# SYSTEM.net
KiCad netlist of a schematic drawn in Altium Designer
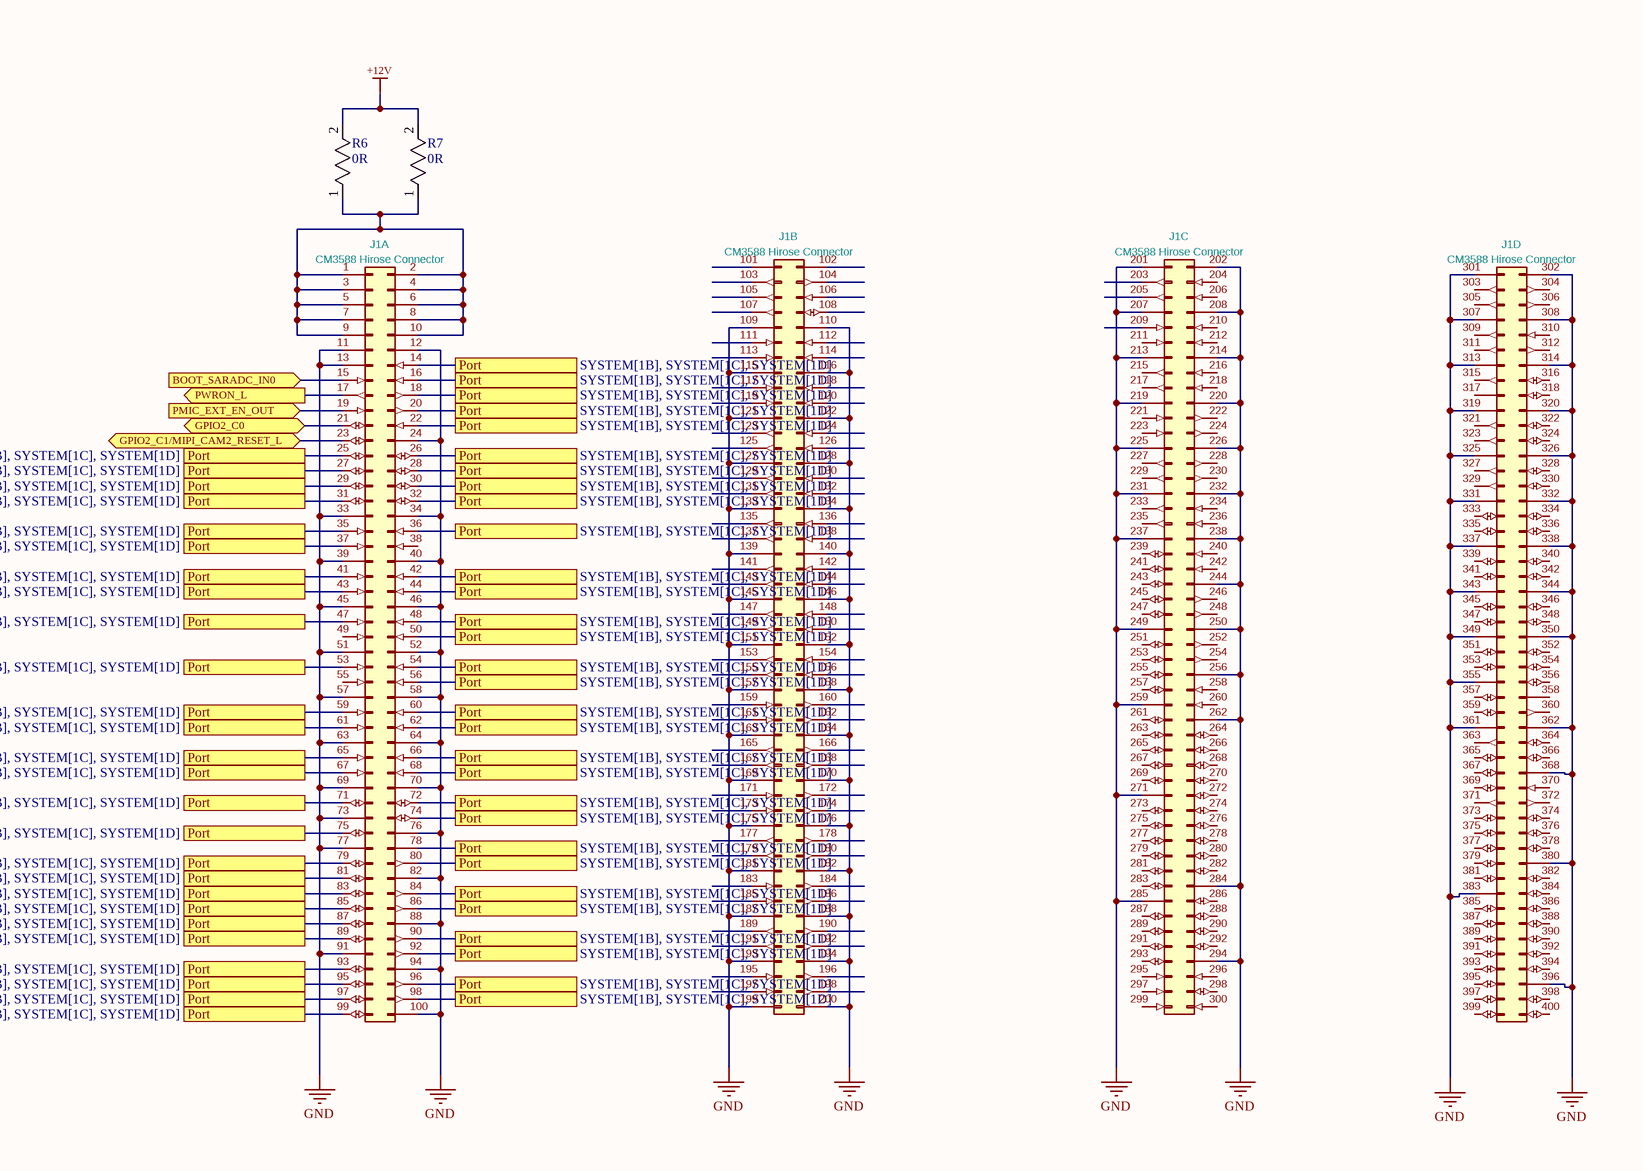
[diagram p0: SYSTEM.SchDoc, right]

(export (version "E")
  (design (tool "Eeschema 10.0.6"))
  (components
    (comp (ref "J1")
      (value "CM3588 Hirose Connector")
      (footprint "CM3588")
      (libsource (lib "cm3588") (part "CM3588"))
    )
    (comp (ref "R6")
      (value "0R")
      (footprint "RES_0816_SUS")
      (description "Zero Ohm Resistor, Jumper, 0603 [1608 Metric], Thick Film, 100 mW, 1 A, Surface Mount")
      (fields
        (field (name "MANUFACTURER") "NIC Components")
        (field (name "MANUFACTURER PART NUMBER") "NRC06ZOTRF")
      )
      (libsource (lib "RES_SMD_0603") (part "RG1608P-104-B-T5"))
    )
    (comp (ref "R7")
      (value "0R")
      (footprint "RES_0816_SUS")
      (description "Zero Ohm Resistor, Jumper, 0603 [1608 Metric], Thick Film, 100 mW, 1 A, Surface Mount")
      (fields
        (field (name "MANUFACTURER") "NIC Components")
        (field (name "MANUFACTURER PART NUMBER") "NRC06ZOTRF")
      )
      (libsource (lib "RES_SMD_0603") (part "RG1608P-104-B-T5"))
    )
  )
  (nets
    (net (code "1") (name "+12V") (class "Default")
      (node (ref "R6") (pin "2") (pinfunction "2_2") (pintype "passive"))
      (node (ref "R7") (pin "2") (pinfunction "2_2") (pintype "passive"))
    )
    (net (code "2") (name "/BOOT_SARADC_IN0") (class "Default")
      (node (ref "J1") (pin "15") (pinfunction "BOOT_SARADC_IN0_15") (pintype "input"))
    )
    (net (code "3") (name "/GPIO2_C0") (class "Default")
      (node (ref "J1") (pin "21") (pinfunction "GPIO2_C0_21") (pintype "bidirectional"))
    )
    (net (code "4") (name "/GPIO2_C1{slash}MIPI_CAM2_RESET_L") (class "Default")
      (node (ref "J1") (pin "23") (pinfunction "GPIO2_C1/MIPI_CAM2_RESET_L_23") (pintype "bidirectional"))
    )
    (net (code "5") (name "/PMIC_EXT_EN_OUT") (class "Default")
      (node (ref "J1") (pin "19") (pinfunction "PMIC_EXT_EN_OUT_19") (pintype "input"))
    )
    (net (code "6") (name "/PWRON_L") (class "Default")
      (node (ref "J1") (pin "17") (pinfunction "PWRON_L_17") (pintype "output"))
    )
    (net (code "7") (name "/Port") (class "Default")
      (node (ref "J1") (pin "14") (pinfunction "SARADC_VIN6_HW_ID2_14") (pintype "input"))
      (node (ref "J1") (pin "16") (pinfunction "RESET_L_16") (pintype "input"))
      (node (ref "J1") (pin "18") (pinfunction "VDC_MODE_18") (pintype "output"))
      (node (ref "J1") (pin "20") (pinfunction "UART2_TX_M0_DEBUG_20") (pintype "output"))
      (node (ref "J1") (pin "22") (pinfunction "UART2_RX_M0_DEBUG_22") (pintype "input"))
      (node (ref "J1") (pin "25") (pinfunction "GPIO2_C2/MIPI_CAM2_PDN_L_25") (pintype "bidirectional"))
      (node (ref "J1") (pin "26") (pinfunction "GPIO4_C2_26") (pintype "bidirectional"))
      (node (ref "J1") (pin "27") (pinfunction "GPIO2_C3_27") (pintype "bidirectional"))
      (node (ref "J1") (pin "28") (pinfunction "GPIO4_C3_28") (pintype "bidirectional"))
      (node (ref "J1") (pin "29") (pinfunction "GPIO2_C4_29") (pintype "bidirectional"))
      (node (ref "J1") (pin "30") (pinfunction "GPIO4_C4_30") (pintype "bidirectional"))
      (node (ref "J1") (pin "31") (pinfunction "GPIO4_C6_31") (pintype "bidirectional"))
      (node (ref "J1") (pin "32") (pinfunction "GPIO4_C5_32") (pintype "bidirectional"))
      (node (ref "J1") (pin "35") (pinfunction "MIPI_CSI1_RX_CLK1P_35") (pintype "input"))
      (node (ref "J1") (pin "36") (pinfunction "MIPI_CSI0_RX_CLK1P_36") (pintype "input"))
      (node (ref "J1") (pin "37") (pinfunction "MIPI_CSI1_RX_CLK1N_37") (pintype "input"))
      (node (ref "J1") (pin "41") (pinfunction "MIPI_CSI1_RX_D3P_41") (pintype "input"))
      (node (ref "J1") (pin "42") (pinfunction "MIPI_CSI0_RX_D3P_42") (pintype "input"))
      (node (ref "J1") (pin "43") (pinfunction "MIPI_CSI1_RX_D3N_43") (pintype "input"))
      (node (ref "J1") (pin "44") (pinfunction "MIPI_CSI0_RX_D3N_44") (pintype "input"))
      (node (ref "J1") (pin "47") (pinfunction "MIPI_CSI1_RX_D2P_47") (pintype "input"))
      (node (ref "J1") (pin "48") (pinfunction "MIPI_CSI0_RX_D2P_48") (pintype "input"))
      (node (ref "J1") (pin "50") (pinfunction "MIPI_CSI0_RX_D2N_50") (pintype "input"))
      (node (ref "J1") (pin "53") (pinfunction "MIPI_CSI1_RX_CLK0P_53") (pintype "input"))
      (node (ref "J1") (pin "54") (pinfunction "MIPI_CSI0_RX_CLK0P_54") (pintype "input"))
      (node (ref "J1") (pin "56") (pinfunction "MIPI_CSI0_RX_CLK0N_56") (pintype "input"))
      (node (ref "J1") (pin "59") (pinfunction "MIPI_CSI1_RX_D1P_59") (pintype "input"))
      (node (ref "J1") (pin "60") (pinfunction "MIPI_CSI0_RX_D1P_60") (pintype "input"))
      (node (ref "J1") (pin "61") (pinfunction "MIPI_CSI1_RX_D1N_61") (pintype "input"))
      (node (ref "J1") (pin "62") (pinfunction "MIPI_CSI0_RX_D1N_62") (pintype "input"))
      (node (ref "J1") (pin "65") (pinfunction "MIPI_CSI1_RX_D0P_65") (pintype "input"))
      (node (ref "J1") (pin "66") (pinfunction "MIPI_CSI0_RX_D0P_66") (pintype "input"))
      (node (ref "J1") (pin "67") (pinfunction "MIPI_CSI1_RX_D0N_67") (pintype "input"))
      (node (ref "J1") (pin "68") (pinfunction "MIPI_CSI0_RX_D0N_68") (pintype "input"))
      (node (ref "J1") (pin "71") (pinfunction "GPIO1_B6_71") (pintype "bidirectional"))
      (node (ref "J1") (pin "72") (pinfunction "LED3_25GLAN_25GLED_72") (pintype "bidirectional"))
      (node (ref "J1") (pin "74") (pinfunction "LED2_25GLAN_1GLED_74") (pintype "bidirectional"))
      (node (ref "J1") (pin "75") (pinfunction "GPIO1_B7_75") (pintype "bidirectional"))
      (node (ref "J1") (pin "78") (pinfunction "P25G_MDIP0_78") (pintype "passive"))
      (node (ref "J1") (pin "79") (pinfunction "GPIO2_A6_79") (pintype "bidirectional"))
      (node (ref "J1") (pin "80") (pinfunction "P25G_MDIN0_80") (pintype "output"))
      (node (ref "J1") (pin "81") (pinfunction "GPIO2_A7_81") (pintype "bidirectional"))
      (node (ref "J1") (pin "83") (pinfunction "GPIO2_B0_83") (pintype "bidirectional"))
      (node (ref "J1") (pin "84") (pinfunction "P25G_MDIP1_84") (pintype "output"))
      (node (ref "J1") (pin "85") (pinfunction "GPIO2_B1_GPIO,_85") (pintype "bidirectional"))
      (node (ref "J1") (pin "86") (pinfunction "P25G_MDIN1_86") (pintype "output"))
      (node (ref "J1") (pin "87") (pinfunction "GPIO2_B2_87") (pintype "bidirectional"))
      (node (ref "J1") (pin "89") (pinfunction "GPIO2_B3_89") (pintype "bidirectional"))
      (node (ref "J1") (pin "90") (pinfunction "P25G_MDIP2_90") (pintype "output"))
      (node (ref "J1") (pin "92") (pinfunction "P25G_MDIN2_92") (pintype "output"))
      (node (ref "J1") (pin "93") (pinfunction "GPIO2_B4_93") (pintype "bidirectional"))
      (node (ref "J1") (pin "95") (pinfunction "GPIO2_B5_95") (pintype "bidirectional"))
      (node (ref "J1") (pin "96") (pinfunction "P25G_MDIP3_96") (pintype "output"))
      (node (ref "J1") (pin "97") (pinfunction "GPIO2_B6_97") (pintype "bidirectional"))
      (node (ref "J1") (pin "98") (pinfunction "P25G_MDIN3_98") (pintype "output"))
      (node (ref "J1") (pin "99") (pinfunction "GPIO2_B7_99") (pintype "bidirectional"))
    )
    (net (code "8") (name "GND") (class "Default")
      (node (ref "J1") (pin "100") (pinfunction "GND_100") (pintype "passive"))
      (node (ref "J1") (pin "109") (pinfunction "GND_109") (pintype "passive"))
      (node (ref "J1") (pin "11") (pinfunction "GND_11") (pintype "passive"))
      (node (ref "J1") (pin "110") (pinfunction "GND_110") (pintype "passive"))
      (node (ref "J1") (pin "115") (pinfunction "GND_115") (pintype "passive"))
      (node (ref "J1") (pin "116") (pinfunction "GND_116") (pintype "passive"))
      (node (ref "J1") (pin "12") (pinfunction "GND_12") (pintype "passive"))
      (node (ref "J1") (pin "121") (pinfunction "GND_121") (pintype "passive"))
      (node (ref "J1") (pin "122") (pinfunction "GND_122") (pintype "passive"))
      (node (ref "J1") (pin "127") (pinfunction "GND_127") (pintype "passive"))
      (node (ref "J1") (pin "128") (pinfunction "GND_128") (pintype "passive"))
      (node (ref "J1") (pin "13") (pinfunction "GND_13") (pintype "passive"))
      (node (ref "J1") (pin "133") (pinfunction "GND_133") (pintype "passive"))
      (node (ref "J1") (pin "134") (pinfunction "GND_134") (pintype "passive"))
      (node (ref "J1") (pin "139") (pinfunction "GND_139") (pintype "passive"))
      (node (ref "J1") (pin "140") (pinfunction "GND_140") (pintype "passive"))
      (node (ref "J1") (pin "145") (pinfunction "GND_145") (pintype "passive"))
      (node (ref "J1") (pin "146") (pinfunction "GND_146") (pintype "passive"))
      (node (ref "J1") (pin "151") (pinfunction "GND_151") (pintype "passive"))
      (node (ref "J1") (pin "152") (pinfunction "GND_152") (pintype "passive"))
      (node (ref "J1") (pin "157") (pinfunction "GND_157") (pintype "passive"))
      (node (ref "J1") (pin "158") (pinfunction "GND_158") (pintype "passive"))
      (node (ref "J1") (pin "163") (pinfunction "GND_163") (pintype "passive"))
      (node (ref "J1") (pin "164") (pinfunction "GND_164") (pintype "passive"))
      (node (ref "J1") (pin "169") (pinfunction "GND_169") (pintype "passive"))
      (node (ref "J1") (pin "170") (pinfunction "GND_170") (pintype "passive"))
      (node (ref "J1") (pin "175") (pinfunction "GND_175") (pintype "passive"))
      (node (ref "J1") (pin "176") (pinfunction "GND_176") (pintype "passive"))
      (node (ref "J1") (pin "181") (pinfunction "GND_181") (pintype "passive"))
      (node (ref "J1") (pin "182") (pinfunction "GND_182") (pintype "passive"))
      (node (ref "J1") (pin "187") (pinfunction "GND_187") (pintype "passive"))
      (node (ref "J1") (pin "188") (pinfunction "GND_188") (pintype "passive"))
      (node (ref "J1") (pin "193") (pinfunction "GND_193") (pintype "passive"))
      (node (ref "J1") (pin "194") (pinfunction "GND_194") (pintype "passive"))
      (node (ref "J1") (pin "199") (pinfunction "GND_199") (pintype "passive"))
      (node (ref "J1") (pin "200") (pinfunction "GND_200") (pintype "passive"))
      (node (ref "J1") (pin "201") (pinfunction "GND_201") (pintype "passive"))
      (node (ref "J1") (pin "202") (pinfunction "GND_202") (pintype "passive"))
      (node (ref "J1") (pin "207") (pinfunction "GND_207") (pintype "passive"))
      (node (ref "J1") (pin "208") (pinfunction "GND_208") (pintype "passive"))
      (node (ref "J1") (pin "213") (pinfunction "GND_213") (pintype "passive"))
      (node (ref "J1") (pin "214") (pinfunction "GND_214") (pintype "passive"))
      (node (ref "J1") (pin "219") (pinfunction "GND_219") (pintype "passive"))
      (node (ref "J1") (pin "220") (pinfunction "GND_220") (pintype "passive"))
      (node (ref "J1") (pin "225") (pinfunction "GND_225") (pintype "passive"))
      (node (ref "J1") (pin "226") (pinfunction "GND_226") (pintype "passive"))
      (node (ref "J1") (pin "231") (pinfunction "GND_231") (pintype "passive"))
      (node (ref "J1") (pin "232") (pinfunction "GND_232") (pintype "passive"))
      (node (ref "J1") (pin "237") (pinfunction "GND_237") (pintype "passive"))
      (node (ref "J1") (pin "238") (pinfunction "GND_238") (pintype "passive"))
      (node (ref "J1") (pin "24") (pinfunction "GND_24") (pintype "passive"))
      (node (ref "J1") (pin "244") (pinfunction "GND_244") (pintype "passive"))
      (node (ref "J1") (pin "249") (pinfunction "GND_249") (pintype "passive"))
      (node (ref "J1") (pin "250") (pinfunction "GND_250") (pintype "passive"))
      (node (ref "J1") (pin "256") (pinfunction "GND_256") (pintype "passive"))
      (node (ref "J1") (pin "259") (pinfunction "GND_259") (pintype "passive"))
      (node (ref "J1") (pin "262") (pinfunction "GND_262") (pintype "passive"))
      (node (ref "J1") (pin "271") (pinfunction "GND_271") (pintype "passive"))
      (node (ref "J1") (pin "284") (pinfunction "GND_284") (pintype "passive"))
      (node (ref "J1") (pin "285") (pinfunction "GND_285") (pintype "passive"))
      (node (ref "J1") (pin "294") (pinfunction "GND_294") (pintype "passive"))
      (node (ref "J1") (pin "301") (pinfunction "GND_301") (pintype "passive"))
      (node (ref "J1") (pin "302") (pinfunction "GND_302") (pintype "passive"))
      (node (ref "J1") (pin "307") (pinfunction "GND_307") (pintype "passive"))
      (node (ref "J1") (pin "308") (pinfunction "GND_308") (pintype "passive"))
      (node (ref "J1") (pin "313") (pinfunction "GND_313") (pintype "passive"))
      (node (ref "J1") (pin "314") (pinfunction "GND_314") (pintype "passive"))
      (node (ref "J1") (pin "319") (pinfunction "GND_319") (pintype "passive"))
      (node (ref "J1") (pin "320") (pinfunction "GND_320") (pintype "passive"))
      (node (ref "J1") (pin "325") (pinfunction "GND_325") (pintype "passive"))
      (node (ref "J1") (pin "326") (pinfunction "GND_326") (pintype "passive"))
      (node (ref "J1") (pin "33") (pinfunction "GND_33") (pintype "power_in"))
      (node (ref "J1") (pin "331") (pinfunction "GND_331") (pintype "passive"))
      (node (ref "J1") (pin "332") (pinfunction "GND_332") (pintype "passive"))
      (node (ref "J1") (pin "337") (pinfunction "GND_337") (pintype "passive"))
      (node (ref "J1") (pin "338") (pinfunction "GND_338") (pintype "passive"))
      (node (ref "J1") (pin "34") (pinfunction "GND_34") (pintype "power_in"))
      (node (ref "J1") (pin "343") (pinfunction "GND_343") (pintype "passive"))
      (node (ref "J1") (pin "344") (pinfunction "GND_344") (pintype "passive"))
      (node (ref "J1") (pin "349") (pinfunction "GND_349") (pintype "passive"))
      (node (ref "J1") (pin "350") (pinfunction "GND_350") (pintype "passive"))
      (node (ref "J1") (pin "355") (pinfunction "GND_355") (pintype "passive"))
      (node (ref "J1") (pin "361") (pinfunction "GND_361") (pintype "passive"))
      (node (ref "J1") (pin "362") (pinfunction "GND_362") (pintype "passive"))
      (node (ref "J1") (pin "368") (pinfunction "GND_368") (pintype "passive"))
      (node (ref "J1") (pin "380") (pinfunction "GND_380") (pintype "passive"))
      (node (ref "J1") (pin "383") (pinfunction "GND_383") (pintype "passive"))
      (node (ref "J1") (pin "39") (pinfunction "GND_39") (pintype "passive"))
      (node (ref "J1") (pin "396") (pinfunction "GND_396") (pintype "passive"))
      (node (ref "J1") (pin "40") (pinfunction "GND_40") (pintype "passive"))
      (node (ref "J1") (pin "45") (pinfunction "GND_45") (pintype "passive"))
      (node (ref "J1") (pin "46") (pinfunction "GND_46") (pintype "passive"))
      (node (ref "J1") (pin "51") (pinfunction "GND_51") (pintype "passive"))
      (node (ref "J1") (pin "52") (pinfunction "GND_52") (pintype "passive"))
      (node (ref "J1") (pin "57") (pinfunction "GND_57") (pintype "passive"))
      (node (ref "J1") (pin "58") (pinfunction "GND_58") (pintype "passive"))
      (node (ref "J1") (pin "63") (pinfunction "GND_63") (pintype "passive"))
      (node (ref "J1") (pin "64") (pinfunction "GND_64") (pintype "passive"))
      (node (ref "J1") (pin "69") (pinfunction "GND_69") (pintype "passive"))
      (node (ref "J1") (pin "70") (pinfunction "GND_70") (pintype "passive"))
      (node (ref "J1") (pin "73") (pinfunction "GND_73") (pintype "passive"))
      (node (ref "J1") (pin "76") (pinfunction "GND_76") (pintype "passive"))
      (node (ref "J1") (pin "77") (pinfunction "GND_77") (pintype "passive"))
      (node (ref "J1") (pin "82") (pinfunction "GND_82") (pintype "passive"))
      (node (ref "J1") (pin "88") (pinfunction "GND_88") (pintype "passive"))
      (node (ref "J1") (pin "91") (pinfunction "GND_91") (pintype "passive"))
      (node (ref "J1") (pin "94") (pinfunction "GND_94") (pintype "passive"))
    )
    (net (code "9") (name "Net-(J1A-VDD_DCIN-Pad1)") (class "Default")
      (node (ref "J1") (pin "1") (pinfunction "VDD_DCIN_1") (pintype "power_in"))
      (node (ref "J1") (pin "10") (pinfunction "VDD_DCIN_10") (pintype "power_in"))
      (node (ref "J1") (pin "2") (pinfunction "VDD_DCIN_2") (pintype "power_in"))
      (node (ref "J1") (pin "3") (pinfunction "VDD_DCIN_3") (pintype "power_in"))
      (node (ref "J1") (pin "4") (pinfunction "VDD_DCIN_4") (pintype "power_in"))
      (node (ref "J1") (pin "5") (pinfunction "VDD_DCIN_5") (pintype "power_in"))
      (node (ref "J1") (pin "6") (pinfunction "VDD_DCIN_6") (pintype "power_in"))
      (node (ref "J1") (pin "7") (pinfunction "VDD_DCIN_7") (pintype "power_in"))
      (node (ref "J1") (pin "8") (pinfunction "VDD_DCIN_8") (pintype "power_in"))
      (node (ref "J1") (pin "9") (pinfunction "VDD_DCIN_9") (pintype "power_in"))
      (node (ref "R6") (pin "1") (pinfunction "1_1") (pintype "passive"))
      (node (ref "R7") (pin "1") (pinfunction "1_1") (pintype "passive"))
    )
    (net (code "10") (name "unconnected-(J1A-MIPI_CSI0_RX_CLK1N-Pad38)") (class "Default")
      (node (ref "J1") (pin "38") (pinfunction "MIPI_CSI0_RX_CLK1N_38") (pintype "input"))
    )
    (net (code "11") (name "unconnected-(J1A-MIPI_CSI1_RX_CLK0N-Pad55)") (class "Default")
      (node (ref "J1") (pin "55") (pinfunction "MIPI_CSI1_RX_CLK0N_55") (pintype "input"))
    )
    (net (code "12") (name "unconnected-(J1A-MIPI_CSI1_RX_D2N-Pad49)") (class "Default")
      (node (ref "J1") (pin "49") (pinfunction "MIPI_CSI1_RX_D2N_49") (pintype "input"))
    )
    (net (code "13") (name "unconnected-(J1B-GND_AUDUO-Pad102)") (class "Default")
      (node (ref "J1") (pin "102") (pinfunction "GND_AUDUO_102") (pintype "passive"))
    )
    (net (code "14") (name "unconnected-(J1B-GPIO1_C4{slash}HP_DET_L-Pad108)") (class "Default")
      (node (ref "J1") (pin "108") (pinfunction "GPIO1_C4/HP_DET_L_108") (pintype "bidirectional"))
    )
    (net (code "15") (name "unconnected-(J1B-HPL-Pad104)") (class "Default")
      (node (ref "J1") (pin "104") (pinfunction "HPL_104") (pintype "output"))
    )
    (net (code "16") (name "unconnected-(J1B-HPR-Pad103)") (class "Default")
      (node (ref "J1") (pin "103") (pinfunction "HPR_103") (pintype "output"))
    )
    (net (code "17") (name "unconnected-(J1B-I2C7_SCL_M0-Pad107)") (class "Default")
      (node (ref "J1") (pin "107") (pinfunction "I2C7_SCL_M0_107") (pintype "output"))
    )
    (net (code "18") (name "unconnected-(J1B-I2C7_SDA_M0-Pad105)") (class "Default")
      (node (ref "J1") (pin "105") (pinfunction "I2C7_SDA_M0_105") (pintype "output"))
    )
    (net (code "19") (name "unconnected-(J1B-MIC_IN-Pad106)") (class "Default")
      (node (ref "J1") (pin "106") (pinfunction "MIC_IN_106") (pintype "input"))
    )
    (net (code "20") (name "unconnected-(J1B-MIPI_DPHY0_RX_CLKN-Pad120)") (class "Default")
      (node (ref "J1") (pin "120") (pinfunction "MIPI_DPHY0_RX_CLKN_120") (pintype "input"))
    )
    (net (code "21") (name "unconnected-(J1B-MIPI_DPHY0_RX_CLKP-Pad118)") (class "Default")
      (node (ref "J1") (pin "118") (pinfunction "MIPI_DPHY0_RX_CLKP_118") (pintype "input"))
    )
    (net (code "22") (name "unconnected-(J1B-MIPI_DPHY0_RX_D0N-Pad126)") (class "Default")
      (node (ref "J1") (pin "126") (pinfunction "MIPI_DPHY0_RX_D0N_126") (pintype "input"))
    )
    (net (code "23") (name "unconnected-(J1B-MIPI_DPHY0_RX_D0P-Pad124)") (class "Default")
      (node (ref "J1") (pin "124") (pinfunction "MIPI_DPHY0_RX_D0P_124") (pintype "input"))
    )
    (net (code "24") (name "unconnected-(J1B-MIPI_DPHY0_RX_D1N-Pad119)") (class "Default")
      (node (ref "J1") (pin "119") (pinfunction "MIPI_DPHY0_RX_D1N_119") (pintype "input"))
    )
    (net (code "25") (name "unconnected-(J1B-MIPI_DPHY0_RX_D1P-Pad117)") (class "Default")
      (node (ref "J1") (pin "117") (pinfunction "MIPI_DPHY0_RX_D1P_117") (pintype "input"))
    )
    (net (code "26") (name "unconnected-(J1B-MIPI_DPHY0_RX_D2N-Pad113)") (class "Default")
      (node (ref "J1") (pin "113") (pinfunction "MIPI_DPHY0_RX_D2N_113") (pintype "input"))
    )
    (net (code "27") (name "unconnected-(J1B-MIPI_DPHY0_RX_D2P-Pad111)") (class "Default")
      (node (ref "J1") (pin "111") (pinfunction "MIPI_DPHY0_RX_D2P_111") (pintype "input"))
    )
    (net (code "28") (name "unconnected-(J1B-MIPI_DPHY0_RX_D3N-Pad114)") (class "Default")
      (node (ref "J1") (pin "114") (pinfunction "MIPI_DPHY0_RX_D3N_114") (pintype "input"))
    )
    (net (code "29") (name "unconnected-(J1B-MIPI_DPHY0_RX_D3P-Pad112)") (class "Default")
      (node (ref "J1") (pin "112") (pinfunction "MIPI_DPHY0_RX_D3P_112") (pintype "input"))
    )
    (net (code "30") (name "unconnected-(J1B-MIPI_DPHY0_TX_CLKN-Pad137)") (class "Default")
      (node (ref "J1") (pin "137") (pinfunction "MIPI_DPHY0_TX_CLKN_137") (pintype "output"))
    )
    (net (code "31") (name "unconnected-(J1B-MIPI_DPHY0_TX_CLKP-Pad135)") (class "Default")
      (node (ref "J1") (pin "135") (pinfunction "MIPI_DPHY0_TX_CLKP_135") (pintype "output"))
    )
    (net (code "32") (name "unconnected-(J1B-MIPI_DPHY0_TX_D0N-Pad149)") (class "Default")
      (node (ref "J1") (pin "149") (pinfunction "MIPI_DPHY0_TX_D0N_149") (pintype "output"))
    )
    (net (code "33") (name "unconnected-(J1B-MIPI_DPHY0_TX_D0P-Pad147)") (class "Default")
      (node (ref "J1") (pin "147") (pinfunction "MIPI_DPHY0_TX_D0P_147") (pintype "output"))
    )
    (net (code "34") (name "unconnected-(J1B-MIPI_DPHY0_TX_D1N-Pad143)") (class "Default")
      (node (ref "J1") (pin "143") (pinfunction "MIPI_DPHY0_TX_D1N_143") (pintype "output"))
    )
    (net (code "35") (name "unconnected-(J1B-MIPI_DPHY0_TX_D1P-Pad141)") (class "Default")
      (node (ref "J1") (pin "141") (pinfunction "MIPI_DPHY0_TX_D1P_141") (pintype "output"))
    )
    (net (code "36") (name "unconnected-(J1B-MIPI_DPHY0_TX_D2N-Pad131)") (class "Default")
      (node (ref "J1") (pin "131") (pinfunction "MIPI_DPHY0_TX_D2N_131") (pintype "output"))
    )
    (net (code "37") (name "unconnected-(J1B-MIPI_DPHY0_TX_D2P-Pad129)") (class "Default")
      (node (ref "J1") (pin "129") (pinfunction "MIPI_DPHY0_TX_D2P_129") (pintype "output"))
    )
    (net (code "38") (name "unconnected-(J1B-MIPI_DPHY0_TX_D3N-Pad125)") (class "Default")
      (node (ref "J1") (pin "125") (pinfunction "MIPI_DPHY0_TX_D3N_125") (pintype "output"))
    )
    (net (code "39") (name "unconnected-(J1B-MIPI_DPHY0_TX_D3P-Pad123)") (class "Default")
      (node (ref "J1") (pin "123") (pinfunction "MIPI_DPHY0_TX_D3P_123") (pintype "output"))
    )
    (net (code "40") (name "unconnected-(J1B-MIPI_DPHY1_RX_CLKN-Pad144)") (class "Default")
      (node (ref "J1") (pin "144") (pinfunction "MIPI_DPHY1_RX_CLKN_144") (pintype "input"))
    )
    (net (code "41") (name "unconnected-(J1B-MIPI_DPHY1_RX_CLKP-Pad142)") (class "Default")
      (node (ref "J1") (pin "142") (pinfunction "MIPI_DPHY1_RX_CLKP_142") (pintype "input"))
    )
    (net (code "42") (name "unconnected-(J1B-MIPI_DPHY1_RX_D0N-Pad156)") (class "Default")
      (node (ref "J1") (pin "156") (pinfunction "MIPI_DPHY1_RX_D0N_156") (pintype "input"))
    )
    (net (code "43") (name "unconnected-(J1B-MIPI_DPHY1_RX_D0P-Pad154)") (class "Default")
      (node (ref "J1") (pin "154") (pinfunction "MIPI_DPHY1_RX_D0P_154") (pintype "input"))
    )
    (net (code "44") (name "unconnected-(J1B-MIPI_DPHY1_RX_D1N-Pad150)") (class "Default")
      (node (ref "J1") (pin "150") (pinfunction "MIPI_DPHY1_RX_D1N_150") (pintype "input"))
    )
    (net (code "45") (name "unconnected-(J1B-MIPI_DPHY1_RX_D1P-Pad148)") (class "Default")
      (node (ref "J1") (pin "148") (pinfunction "MIPI_DPHY1_RX_D1P_148") (pintype "input"))
    )
    (net (code "46") (name "unconnected-(J1B-MIPI_DPHY1_RX_D2N-Pad138)") (class "Default")
      (node (ref "J1") (pin "138") (pinfunction "MIPI_DPHY1_RX_D2N_138") (pintype "input"))
    )
    (net (code "47") (name "unconnected-(J1B-MIPI_DPHY1_RX_D2P-Pad136)") (class "Default")
      (node (ref "J1") (pin "136") (pinfunction "MIPI_DPHY1_RX_D2P_136") (pintype "input"))
    )
    (net (code "48") (name "unconnected-(J1B-MIPI_DPHY1_RX_D3N-Pad132)") (class "Default")
      (node (ref "J1") (pin "132") (pinfunction "MIPI_DPHY1_RX_D3N_132") (pintype "input"))
    )
    (net (code "49") (name "unconnected-(J1B-MIPI_DPHY1_RX_D3P-Pad130)") (class "Default")
      (node (ref "J1") (pin "130") (pinfunction "MIPI_DPHY1_RX_D3P_130") (pintype "input"))
    )
    (net (code "50") (name "unconnected-(J1B-MIPI_DPHY1_TX_CLKN-Pad174)") (class "Default")
      (node (ref "J1") (pin "174") (pinfunction "MIPI_DPHY1_TX_CLKN_174") (pintype "output"))
    )
    (net (code "51") (name "unconnected-(J1B-MIPI_DPHY1_TX_CLKP-Pad172)") (class "Default")
      (node (ref "J1") (pin "172") (pinfunction "MIPI_DPHY1_TX_CLKP_172") (pintype "output"))
    )
    (net (code "52") (name "unconnected-(J1B-MIPI_DPHY1_TX_D0N-Pad186)") (class "Default")
      (node (ref "J1") (pin "186") (pinfunction "MIPI_DPHY1_TX_D0N_186") (pintype "output"))
    )
    (net (code "53") (name "unconnected-(J1B-MIPI_DPHY1_TX_D0P-Pad184)") (class "Default")
      (node (ref "J1") (pin "184") (pinfunction "MIPI_DPHY1_TX_D0P_184") (pintype "output"))
    )
    (net (code "54") (name "unconnected-(J1B-MIPI_DPHY1_TX_D1N-Pad180)") (class "Default")
      (node (ref "J1") (pin "180") (pinfunction "MIPI_DPHY1_TX_D1N_180") (pintype "output"))
    )
    (net (code "55") (name "unconnected-(J1B-MIPI_DPHY1_TX_D1P-Pad178)") (class "Default")
      (node (ref "J1") (pin "178") (pinfunction "MIPI_DPHY1_TX_D1P_178") (pintype "output"))
    )
    (net (code "56") (name "unconnected-(J1B-MIPI_DPHY1_TX_D2N-Pad168)") (class "Default")
      (node (ref "J1") (pin "168") (pinfunction "MIPI_DPHY1_TX_D2N_168") (pintype "output"))
    )
    (net (code "57") (name "unconnected-(J1B-MIPI_DPHY1_TX_D2P-Pad166)") (class "Default")
      (node (ref "J1") (pin "166") (pinfunction "MIPI_DPHY1_TX_D2P_166") (pintype "output"))
    )
    (net (code "58") (name "unconnected-(J1B-MIPI_DPHY1_TX_D3N-Pad162)") (class "Default")
      (node (ref "J1") (pin "162") (pinfunction "MIPI_DPHY1_TX_D3N_162") (pintype "output"))
    )
    (net (code "59") (name "unconnected-(J1B-MIPI_DPHY1_TX_D3P-Pad160)") (class "Default")
      (node (ref "J1") (pin "160") (pinfunction "MIPI_DPHY1_TX_D3P_160") (pintype "output"))
    )
    (net (code "60") (name "unconnected-(J1B-RECOVERY-Pad101)") (class "Default")
      (node (ref "J1") (pin "101") (pinfunction "RECOVERY_101") (pintype "passive"))
    )
    (net (code "61") (name "unconnected-(J1B-TYPEC0_OTG_DM-Pad192)") (class "Default")
      (node (ref "J1") (pin "192") (pinfunction "TYPEC0_OTG_DM_192") (pintype "output"))
    )
    (net (code "62") (name "unconnected-(J1B-TYPEC0_OTG_DP-Pad190)") (class "Default")
      (node (ref "J1") (pin "190") (pinfunction "TYPEC0_OTG_DP_190") (pintype "output"))
    )
    (net (code "63") (name "unconnected-(J1B-TYPEC0_SSRX1N-Pad173)") (class "Default")
      (node (ref "J1") (pin "173") (pinfunction "TYPEC0_SSRX1N_173") (pintype "input"))
    )
    (net (code "64") (name "unconnected-(J1B-TYPEC0_SSRX1P-Pad171)") (class "Default")
      (node (ref "J1") (pin "171") (pinfunction "TYPEC0_SSRX1P_171") (pintype "input"))
    )
    (net (code "65") (name "unconnected-(J1B-TYPEC0_SSRX2N-Pad161)") (class "Default")
      (node (ref "J1") (pin "161") (pinfunction "TYPEC0_SSRX2N_161") (pintype "input"))
    )
    (net (code "66") (name "unconnected-(J1B-TYPEC0_SSRX2P-Pad159)") (class "Default")
      (node (ref "J1") (pin "159") (pinfunction "TYPEC0_SSRX2P_159") (pintype "input"))
    )
    (net (code "67") (name "unconnected-(J1B-TYPEC0_SSTX1N-Pad167)") (class "Default")
      (node (ref "J1") (pin "167") (pinfunction "TYPEC0_SSTX1N_167") (pintype "output"))
    )
    (net (code "68") (name "unconnected-(J1B-TYPEC0_SSTX1P-Pad165)") (class "Default")
      (node (ref "J1") (pin "165") (pinfunction "TYPEC0_SSTX1P_165") (pintype "output"))
    )
    (net (code "69") (name "unconnected-(J1B-TYPEC0_SSTX2N-Pad155)") (class "Default")
      (node (ref "J1") (pin "155") (pinfunction "TYPEC0_SSTX2N_155") (pintype "output"))
    )
    (net (code "70") (name "unconnected-(J1B-TYPEC0_SSTX2P-Pad153)") (class "Default")
      (node (ref "J1") (pin "153") (pinfunction "TYPEC0_SSTX2P_153") (pintype "output"))
    )
    (net (code "71") (name "unconnected-(J1B-TYPEC1_OTG_DM-Pad198)") (class "Default")
      (node (ref "J1") (pin "198") (pinfunction "TYPEC1_OTG_DM_198") (pintype "output"))
    )
    (net (code "72") (name "unconnected-(J1B-TYPEC1_OTG_DP-Pad196)") (class "Default")
      (node (ref "J1") (pin "196") (pinfunction "TYPEC1_OTG_DP_196") (pintype "output"))
    )
    (net (code "73") (name "unconnected-(J1B-TYPEC1_SSRX1N-Pad197)") (class "Default")
      (node (ref "J1") (pin "197") (pinfunction "TYPEC1_SSRX1N_197") (pintype "input"))
    )
    (net (code "74") (name "unconnected-(J1B-TYPEC1_SSRX1P-Pad195)") (class "Default")
      (node (ref "J1") (pin "195") (pinfunction "TYPEC1_SSRX1P_195") (pintype "input"))
    )
    (net (code "75") (name "unconnected-(J1B-TYPEC1_SSRX2N-Pad185)") (class "Default")
      (node (ref "J1") (pin "185") (pinfunction "TYPEC1_SSRX2N_185") (pintype "input"))
    )
    (net (code "76") (name "unconnected-(J1B-TYPEC1_SSRX2P-Pad183)") (class "Default")
      (node (ref "J1") (pin "183") (pinfunction "TYPEC1_SSRX2P_183") (pintype "input"))
    )
    (net (code "77") (name "unconnected-(J1B-TYPEC1_SSTX1N-Pad191)") (class "Default")
      (node (ref "J1") (pin "191") (pinfunction "TYPEC1_SSTX1N_191") (pintype "output"))
    )
    (net (code "78") (name "unconnected-(J1B-TYPEC1_SSTX1P-Pad189)") (class "Default")
      (node (ref "J1") (pin "189") (pinfunction "TYPEC1_SSTX1P_189") (pintype "output"))
    )
    (net (code "79") (name "unconnected-(J1B-TYPEC1_SSTX2N-Pad179)") (class "Default")
      (node (ref "J1") (pin "179") (pinfunction "TYPEC1_SSTX2N_179") (pintype "output"))
    )
    (net (code "80") (name "unconnected-(J1B-TYPEC1_SSTX2P-Pad177)") (class "Default")
      (node (ref "J1") (pin "177") (pinfunction "TYPEC1_SSTX2P_177") (pintype "output"))
    )
    (net (code "81") (name "unconnected-(J1C-GPIO0_B2-Pad247)") (class "Default")
      (node (ref "J1") (pin "247") (pinfunction "GPIO0_B2_247") (pintype "bidirectional"))
    )
    (net (code "82") (name "unconnected-(J1C-GPIO0_C4-Pad270)") (class "Default")
      (node (ref "J1") (pin "270") (pinfunction "GPIO0_C4_270") (pintype "bidirectional"))
    )
    (net (code "83") (name "unconnected-(J1C-GPIO0_C5-Pad272)") (class "Default")
      (node (ref "J1") (pin "272") (pinfunction "GPIO0_C5_272") (pintype "bidirectional"))
    )
    (net (code "84") (name "unconnected-(J1C-GPIO0_C6-Pad274)") (class "Default")
      (node (ref "J1") (pin "274") (pinfunction "GPIO0_C6_274") (pintype "bidirectional"))
    )
    (net (code "85") (name "unconnected-(J1C-GPIO0_D3-Pad264)") (class "Default")
      (node (ref "J1") (pin "264") (pinfunction "GPIO0_D3_264") (pintype "bidirectional"))
    )
    (net (code "86") (name "unconnected-(J1C-GPIO0_D4-Pad266)") (class "Default")
      (node (ref "J1") (pin "266") (pinfunction "GPIO0_D4_266") (pintype "bidirectional"))
    )
    (net (code "87") (name "unconnected-(J1C-GPIO0_D5-Pad268)") (class "Default")
      (node (ref "J1") (pin "268") (pinfunction "GPIO0_D5_268") (pintype "bidirectional"))
    )
    (net (code "88") (name "unconnected-(J1C-GPIO1_A0-Pad273)") (class "Default")
      (node (ref "J1") (pin "273") (pinfunction "GPIO1_A0_273") (pintype "bidirectional"))
    )
    (net (code "89") (name "unconnected-(J1C-GPIO1_A1-Pad275)") (class "Default")
      (node (ref "J1") (pin "275") (pinfunction "GPIO1_A1_275") (pintype "bidirectional"))
    )
    (net (code "90") (name "unconnected-(J1C-GPIO1_A2-Pad277)") (class "Default")
      (node (ref "J1") (pin "277") (pinfunction "GPIO1_A2_277") (pintype "bidirectional"))
    )
    (net (code "91") (name "unconnected-(J1C-GPIO1_A3-Pad279)") (class "Default")
      (node (ref "J1") (pin "279") (pinfunction "GPIO1_A3_279") (pintype "bidirectional"))
    )
    (net (code "92") (name "unconnected-(J1C-GPIO1_A4-Pad281)") (class "Default")
      (node (ref "J1") (pin "281") (pinfunction "GPIO1_A4_281") (pintype "bidirectional"))
    )
    (net (code "93") (name "unconnected-(J1C-GPIO1_A7-Pad283)") (class "Default")
      (node (ref "J1") (pin "283") (pinfunction "GPIO1_A7_283") (pintype "bidirectional"))
    )
    (net (code "94") (name "unconnected-(J1C-GPIO1_B0-Pad276)") (class "Default")
      (node (ref "J1") (pin "276") (pinfunction "GPIO1_B0_276") (pintype "bidirectional"))
    )
    (net (code "95") (name "unconnected-(J1C-GPIO1_B1-Pad278)") (class "Default")
      (node (ref "J1") (pin "278") (pinfunction "GPIO1_B1_278") (pintype "bidirectional"))
    )
    (net (code "96") (name "unconnected-(J1C-GPIO1_B2-Pad280)") (class "Default")
      (node (ref "J1") (pin "280") (pinfunction "GPIO1_B2_280") (pintype "bidirectional"))
    )
    (net (code "97") (name "unconnected-(J1C-GPIO1_B3-Pad282)") (class "Default")
      (node (ref "J1") (pin "282") (pinfunction "GPIO1_B3_282") (pintype "bidirectional"))
    )
    (net (code "98") (name "unconnected-(J1C-GPIO1_B4-Pad290)") (class "Default")
      (node (ref "J1") (pin "290") (pinfunction "GPIO1_B4_290") (pintype "bidirectional"))
    )
    (net (code "99") (name "unconnected-(J1C-GPIO1_B5-Pad292)") (class "Default")
      (node (ref "J1") (pin "292") (pinfunction "GPIO1_B5_292") (pintype "bidirectional"))
    )
    (net (code "100") (name "unconnected-(J1C-GPIO1_C0-Pad245)") (class "Default")
      (node (ref "J1") (pin "245") (pinfunction "GPIO1_C0_245") (pintype "bidirectional"))
    )
    (net (code "101") (name "unconnected-(J1C-GPIO1_C1-Pad243)") (class "Default")
      (node (ref "J1") (pin "243") (pinfunction "GPIO1_C1_243") (pintype "bidirectional"))
    )
    (net (code "102") (name "unconnected-(J1C-GPIO1_D2-Pad239)") (class "Default")
      (node (ref "J1") (pin "239") (pinfunction "GPIO1_D2_239") (pintype "bidirectional"))
    )
    (net (code "103") (name "unconnected-(J1C-GPIO1_D3-Pad241)") (class "Default")
      (node (ref "J1") (pin "241") (pinfunction "GPIO1_D3_241") (pintype "bidirectional"))
    )
    (net (code "104") (name "unconnected-(J1C-GPIO1_D5{slash}HDMIIRX_DET_L-Pad299)") (class "Default")
      (node (ref "J1") (pin "299") (pinfunction "GPIO1_D5/HDMIIRX_DET_L_299") (pintype "input"))
    )
    (net (code "105") (name "unconnected-(J1C-GPIO1_D6-Pad286)") (class "Default")
      (node (ref "J1") (pin "286") (pinfunction "GPIO1_D6_286") (pintype "bidirectional"))
    )
    (net (code "106") (name "unconnected-(J1C-GPIO1_D7-Pad288)") (class "Default")
      (node (ref "J1") (pin "288") (pinfunction "GPIO1_D7_288") (pintype "bidirectional"))
    )
    (net (code "107") (name "unconnected-(J1C-GPIO3_C0-Pad287)") (class "Default")
      (node (ref "J1") (pin "287") (pinfunction "GPIO3_C0_287") (pintype "bidirectional"))
    )
    (net (code "108") (name "unconnected-(J1C-GPIO3_C1-Pad289)") (class "Default")
      (node (ref "J1") (pin "289") (pinfunction "GPIO3_C1_289") (pintype "bidirectional"))
    )
    (net (code "109") (name "unconnected-(J1C-GPIO3_C2-Pad291)") (class "Default")
      (node (ref "J1") (pin "291") (pinfunction "GPIO3_C2_291") (pintype "bidirectional"))
    )
    (net (code "110") (name "unconnected-(J1C-GPIO3_C3-Pad293)") (class "Default")
      (node (ref "J1") (pin "293") (pinfunction "GPIO3_C3_293") (pintype "bidirectional"))
    )
    (net (code "111") (name "unconnected-(J1C-GPIO4_A0-Pad251)") (class "Default")
      (node (ref "J1") (pin "251") (pinfunction "GPIO4_A0_251") (pintype "bidirectional"))
    )
    (net (code "112") (name "unconnected-(J1C-GPIO4_A1-Pad253)") (class "Default")
      (node (ref "J1") (pin "253") (pinfunction "GPIO4_A1_253") (pintype "bidirectional"))
    )
    (net (code "113") (name "unconnected-(J1C-GPIO4_A2-Pad255)") (class "Default")
      (node (ref "J1") (pin "255") (pinfunction "GPIO4_A2_255") (pintype "bidirectional"))
    )
    (net (code "114") (name "unconnected-(J1C-GPIO4_A3-Pad257)") (class "Default")
      (node (ref "J1") (pin "257") (pinfunction "GPIO4_A3_257") (pintype "bidirectional"))
    )
    (net (code "115") (name "unconnected-(J1C-GPIO4_B0-Pad261)") (class "Default")
      (node (ref "J1") (pin "261") (pinfunction "GPIO4_B0_261") (pintype "bidirectional"))
    )
    (net (code "116") (name "unconnected-(J1C-GPIO4_B3-Pad263)") (class "Default")
      (node (ref "J1") (pin "263") (pinfunction "GPIO4_B3_263") (pintype "bidirectional"))
    )
    (net (code "117") (name "unconnected-(J1C-GPIO4_B4-Pad265)") (class "Default")
      (node (ref "J1") (pin "265") (pinfunction "GPIO4_B4_265") (pintype "bidirectional"))
    )
    (net (code "118") (name "unconnected-(J1C-GPIO4_B5-Pad267)") (class "Default")
      (node (ref "J1") (pin "267") (pinfunction "GPIO4_B5_267") (pintype "bidirectional"))
    )
    (net (code "119") (name "unconnected-(J1C-GPIO4_B6-Pad269)") (class "Default")
      (node (ref "J1") (pin "269") (pinfunction "GPIO4_B6_269") (pintype "bidirectional"))
    )
    (net (code "120") (name "unconnected-(J1C-HDMITX0_HPDIN_M0-Pad295)") (class "Default")
      (node (ref "J1") (pin "295") (pinfunction "HDMITX0_HPDIN_M0_295") (pintype "input"))
    )
    (net (code "121") (name "unconnected-(J1C-HDMITX1_HPDIN_M0-Pad297)") (class "Default")
      (node (ref "J1") (pin "297") (pinfunction "HDMITX1_HPDIN_M0_297") (pintype "input"))
    )
    (net (code "122") (name "unconnected-(J1C-I2C6_SCL_M0-Pad296)") (class "Default")
      (node (ref "J1") (pin "296") (pinfunction "I2C6_SCL_M0_296") (pintype "input"))
    )
    (net (code "123") (name "unconnected-(J1C-I2C6_SDA_M0-Pad298)") (class "Default")
      (node (ref "J1") (pin "298") (pinfunction "I2C6_SDA_M0_298") (pintype "bidirectional"))
    )
    (net (code "124") (name "unconnected-(J1C-PCIE20_1_REFCLKN-Pad217)") (class "Default")
      (node (ref "J1") (pin "217") (pinfunction "PCIE20_1_REFCLKN_217") (pintype "output"))
    )
    (net (code "125") (name "unconnected-(J1C-PCIE20_1_REFCLKP-Pad215)") (class "Default")
      (node (ref "J1") (pin "215") (pinfunction "PCIE20_1_REFCLKP_215") (pintype "output"))
    )
    (net (code "126") (name "unconnected-(J1C-PCIE20_1_RXP{slash}SATA30_1_RXP-Pad209)") (class "Default")
      (node (ref "J1") (pin "209") (pinfunction "PCIE20_1_RXP/SATA30_1_RXP_209") (pintype "input"))
    )
    (net (code "127") (name "unconnected-(J1C-PCIE20_1_TXN{slash}SATA30_1_TXN-Pad205)") (class "Default")
      (node (ref "J1") (pin "205") (pinfunction "PCIE20_1_TXN/SATA30_1_TXN_205") (pintype "output"))
    )
    (net (code "128") (name "unconnected-(J1C-PCIE20_1_TXP{slash}SATA30_1_TXP-Pad203)") (class "Default")
      (node (ref "J1") (pin "203") (pinfunction "PCIE20_1_TXP/SATA30_1_TXP_203") (pintype "output"))
    )
    (net (code "129") (name "unconnected-(J1C-PCIE20_2_REFCLKN-Pad229)") (class "Default")
      (node (ref "J1") (pin "229") (pinfunction "PCIE20_2_REFCLKN_229") (pintype "output"))
    )
    (net (code "130") (name "unconnected-(J1C-PCIE20_2_REFCLKP-Pad227)") (class "Default")
      (node (ref "J1") (pin "227") (pinfunction "PCIE20_2_REFCLKP_227") (pintype "output"))
    )
    (net (code "131") (name "unconnected-(J1C-PCIE20_2_RXN{slash}SATA30_2_RXN{slash}USB30_2_SSRXN-Pad223)") (class "Default")
      (node (ref "J1") (pin "223") (pinfunction "PCIE20_2_RXN/SATA30_2_RXN/USB30_2_SSRXN_223") (pintype "input"))
    )
    (net (code "132") (name "unconnected-(J1C-PCIE20_2_RXP{slash}SATA30_2_RXP{slash}USB30_2_SSRXP-Pad221)") (class "Default")
      (node (ref "J1") (pin "221") (pinfunction "PCIE20_2_RXP/SATA30_2_RXP/USB30_2_SSRXP_221") (pintype "input"))
    )
    (net (code "133") (name "unconnected-(J1C-PCIE20_2_TXN{slash}SATA30_2_TXN{slash}USB30_2_SSTXN-Pad235)") (class "Default")
      (node (ref "J1") (pin "235") (pinfunction "PCIE20_2_TXN/SATA30_2_TXN/USB30_2_SSTXN_235") (pintype "output"))
    )
    (net (code "134") (name "unconnected-(J1C-PCIE20_2_TXP{slash}SATA30_2_TXP{slash}USB30_2_SSTXP-Pad233)") (class "Default")
      (node (ref "J1") (pin "233") (pinfunction "PCIE20_2_TXP/SATA30_2_TXP/USB30_2_SSTXP_233") (pintype "output"))
    )
    (net (code "135") (name "unconnected-(J1C-PCIE30_PORT0_REFCLKN_IN-Pad218)") (class "Default")
      (node (ref "J1") (pin "218") (pinfunction "PCIE30_PORT0_REFCLKN_IN_218") (pintype "input"))
    )
    (net (code "136") (name "unconnected-(J1C-PCIE30_PORT0_REFCLKP_IN-Pad216)") (class "Default")
      (node (ref "J1") (pin "216") (pinfunction "PCIE30_PORT0_REFCLKP_IN_216") (pintype "input"))
    )
    (net (code "137") (name "unconnected-(J1C-PCIE30_PORT0_RX0N-Pad206)") (class "Default")
      (node (ref "J1") (pin "206") (pinfunction "PCIE30_PORT0_RX0N_206") (pintype "input"))
    )
    (net (code "138") (name "unconnected-(J1C-PCIE30_PORT0_RX0P-Pad204)") (class "Default")
      (node (ref "J1") (pin "204") (pinfunction "PCIE30_PORT0_RX0P_204") (pintype "input"))
    )
    (net (code "139") (name "unconnected-(J1C-PCIE30_PORT0_RX1N-Pad212)") (class "Default")
      (node (ref "J1") (pin "212") (pinfunction "PCIE30_PORT0_RX1N_212") (pintype "input"))
    )
    (net (code "140") (name "unconnected-(J1C-PCIE30_PORT0_RX1P-Pad210)") (class "Default")
      (node (ref "J1") (pin "210") (pinfunction "PCIE30_PORT0_RX1P_210") (pintype "input"))
    )
    (net (code "141") (name "unconnected-(J1C-PCIE30_PORT0_TX0N-Pad224)") (class "Default")
      (node (ref "J1") (pin "224") (pinfunction "PCIE30_PORT0_TX0N_224") (pintype "output"))
    )
    (net (code "142") (name "unconnected-(J1C-PCIE30_PORT0_TX0P-Pad222)") (class "Default")
      (node (ref "J1") (pin "222") (pinfunction "PCIE30_PORT0_TX0P_222") (pintype "output"))
    )
    (net (code "143") (name "unconnected-(J1C-PCIE30_PORT0_TX1N-Pad230)") (class "Default")
      (node (ref "J1") (pin "230") (pinfunction "PCIE30_PORT0_TX1N_230") (pintype "output"))
    )
    (net (code "144") (name "unconnected-(J1C-PCIE30_PORT0_TX1P-Pad228)") (class "Default")
      (node (ref "J1") (pin "228") (pinfunction "PCIE30_PORT0_TX1P_228") (pintype "output"))
    )
    (net (code "145") (name "unconnected-(J1C-PCIE30_PORT1_REFCLKN_IN-Pad260)") (class "Default")
      (node (ref "J1") (pin "260") (pinfunction "PCIE30_PORT1_REFCLKN_IN_260") (pintype "input"))
    )
    (net (code "146") (name "unconnected-(J1C-PCIE30_PORT1_REFCLKP_IN-Pad258)") (class "Default")
      (node (ref "J1") (pin "258") (pinfunction "PCIE30_PORT1_REFCLKP_IN_258") (pintype "input"))
    )
    (net (code "147") (name "unconnected-(J1C-PCIE30_PORT1_RX2N-Pad236)") (class "Default")
      (node (ref "J1") (pin "236") (pinfunction "PCIE30_PORT1_RX2N_236") (pintype "input"))
    )
    (net (code "148") (name "unconnected-(J1C-PCIE30_PORT1_RX2P-Pad234)") (class "Default")
      (node (ref "J1") (pin "234") (pinfunction "PCIE30_PORT1_RX2P_234") (pintype "input"))
    )
    (net (code "149") (name "unconnected-(J1C-PCIE30_PORT1_RX3N-Pad242)") (class "Default")
      (node (ref "J1") (pin "242") (pinfunction "PCIE30_PORT1_RX3N_242") (pintype "input"))
    )
    (net (code "150") (name "unconnected-(J1C-PCIE30_PORT1_RX3P-Pad240)") (class "Default")
      (node (ref "J1") (pin "240") (pinfunction "PCIE30_PORT1_RX3P_240") (pintype "input"))
    )
    (net (code "151") (name "unconnected-(J1C-PCIE30_PORT1_TX2N-Pad248)") (class "Default")
      (node (ref "J1") (pin "248") (pinfunction "PCIE30_PORT1_TX2N_248") (pintype "output"))
    )
    (net (code "152") (name "unconnected-(J1C-PCIE30_PORT1_TX2P-Pad246)") (class "Default")
      (node (ref "J1") (pin "246") (pinfunction "PCIE30_PORT1_TX2P_246") (pintype "output"))
    )
    (net (code "153") (name "unconnected-(J1C-PCIE30_PORT1_TX3N-Pad254)") (class "Default")
      (node (ref "J1") (pin "254") (pinfunction "PCIE30_PORT1_TX3N_254") (pintype "output"))
    )
    (net (code "154") (name "unconnected-(J1C-PCIE30_PORT1_TX3P-Pad252)") (class "Default")
      (node (ref "J1") (pin "252") (pinfunction "PCIE30_PORT1_TX3P_252") (pintype "output"))
    )
    (net (code "155") (name "unconnected-(J1C-PCPIE20_1_RXN{slash}SATA30_1_RXN-Pad211)") (class "Default")
      (node (ref "J1") (pin "211") (pinfunction "PCPIE20_1_RXN/SATA30_1_RXN_211") (pintype "input"))
    )
    (net (code "156") (name "unconnected-(J1C-VBAT_RTC-Pad300)") (class "Default")
      (node (ref "J1") (pin "300") (pinfunction "VBAT_RTC_300") (pintype "input"))
    )
    (net (code "157") (name "unconnected-(J1D-GPIO0_A4{slash}SDMMC_DET_L-Pad370)") (class "Default")
      (node (ref "J1") (pin "370") (pinfunction "GPIO0_A4/SDMMC_DET_L_370") (pintype "input"))
    )
    (net (code "158") (name "unconnected-(J1D-GPIO3_A0-Pad387)") (class "Default")
      (node (ref "J1") (pin "387") (pinfunction "GPIO3_A0_387") (pintype "bidirectional"))
    )
    (net (code "159") (name "unconnected-(J1D-GPIO3_A1-Pad389)") (class "Default")
      (node (ref "J1") (pin "389") (pinfunction "GPIO3_A1_389") (pintype "bidirectional"))
    )
    (net (code "160") (name "unconnected-(J1D-GPIO3_A2-Pad391)") (class "Default")
      (node (ref "J1") (pin "391") (pinfunction "GPIO3_A2_391") (pintype "bidirectional"))
    )
    (net (code "161") (name "unconnected-(J1D-GPIO3_A3-Pad393)") (class "Default")
      (node (ref "J1") (pin "393") (pinfunction "GPIO3_A3_393") (pintype "bidirectional"))
    )
    (net (code "162") (name "unconnected-(J1D-GPIO3_A4-Pad395)") (class "Default")
      (node (ref "J1") (pin "395") (pinfunction "GPIO3_A4_395") (pintype "bidirectional"))
    )
    (net (code "163") (name "unconnected-(J1D-GPIO3_A5-Pad397)") (class "Default")
      (node (ref "J1") (pin "397") (pinfunction "GPIO3_A5_397") (pintype "bidirectional"))
    )
    (net (code "164") (name "unconnected-(J1D-GPIO3_A6-Pad399)") (class "Default")
      (node (ref "J1") (pin "399") (pinfunction "GPIO3_A6_399") (pintype "bidirectional"))
    )
    (net (code "165") (name "unconnected-(J1D-GPIO3_A7-Pad400)") (class "Default")
      (node (ref "J1") (pin "400") (pinfunction "GPIO3_A7_400") (pintype "bidirectional"))
    )
    (net (code "166") (name "unconnected-(J1D-GPIO3_B0-Pad382)") (class "Default")
      (node (ref "J1") (pin "382") (pinfunction "GPIO3_B0_382") (pintype "bidirectional"))
    )
    (net (code "167") (name "unconnected-(J1D-GPIO3_B1-Pad384)") (class "Default")
      (node (ref "J1") (pin "384") (pinfunction "GPIO3_B1_384") (pintype "bidirectional"))
    )
    (net (code "168") (name "unconnected-(J1D-GPIO3_B2-Pad386)") (class "Default")
      (node (ref "J1") (pin "386") (pinfunction "GPIO3_B2_386") (pintype "bidirectional"))
    )
    (net (code "169") (name "unconnected-(J1D-GPIO3_B3-Pad388)") (class "Default")
      (node (ref "J1") (pin "388") (pinfunction "GPIO3_B3_388") (pintype "bidirectional"))
    )
    (net (code "170") (name "unconnected-(J1D-GPIO3_B4-Pad390)") (class "Default")
      (node (ref "J1") (pin "390") (pinfunction "GPIO3_B4_390") (pintype "bidirectional"))
    )
    (net (code "171") (name "unconnected-(J1D-GPIO3_B5-Pad392)") (class "Default")
      (node (ref "J1") (pin "392") (pinfunction "GPIO3_B5_392") (pintype "bidirectional"))
    )
    (net (code "172") (name "unconnected-(J1D-GPIO3_B6-Pad394)") (class "Default")
      (node (ref "J1") (pin "394") (pinfunction "GPIO3_B6_394") (pintype "bidirectional"))
    )
    (net (code "173") (name "unconnected-(J1D-GPIO3_B7-Pad398)") (class "Default")
      (node (ref "J1") (pin "398") (pinfunction "GPIO3_B7_398") (pintype "bidirectional"))
    )
    (net (code "174") (name "unconnected-(J1D-GPIO3_C7-Pad381)") (class "Default")
      (node (ref "J1") (pin "381") (pinfunction "GPIO3_C7_381") (pintype "bidirectional"))
    )
    (net (code "175") (name "unconnected-(J1D-GPIO3_D0-Pad379)") (class "Default")
      (node (ref "J1") (pin "379") (pinfunction "GPIO3_D0_379") (pintype "bidirectional"))
    )
    (net (code "176") (name "unconnected-(J1D-GPIO3_D5-Pad385)") (class "Default")
      (node (ref "J1") (pin "385") (pinfunction "GPIO3_D5_385") (pintype "bidirectional"))
    )
    (net (code "177") (name "unconnected-(J1D-HDMI0_TX0N_PORT-Pad347)") (class "Default")
      (node (ref "J1") (pin "347") (pinfunction "HDMI0_TX0N_PORT_347") (pintype "bidirectional"))
    )
    (net (code "178") (name "unconnected-(J1D-HDMI0_TX0P_PORT-Pad345)") (class "Default")
      (node (ref "J1") (pin "345") (pinfunction "HDMI0_TX0P_PORT_345") (pintype "bidirectional"))
    )
    (net (code "179") (name "unconnected-(J1D-HDMI0_TX1N_PORT-Pad341)") (class "Default")
      (node (ref "J1") (pin "341") (pinfunction "HDMI0_TX1N_PORT_341") (pintype "bidirectional"))
    )
    (net (code "180") (name "unconnected-(J1D-HDMI0_TX1P_PORT-Pad339)") (class "Default")
      (node (ref "J1") (pin "339") (pinfunction "HDMI0_TX1P_PORT_339") (pintype "bidirectional"))
    )
    (net (code "181") (name "unconnected-(J1D-HDMI0_TX2N_PORT-Pad335)") (class "Default")
      (node (ref "J1") (pin "335") (pinfunction "HDMI0_TX2N_PORT_335") (pintype "bidirectional"))
    )
    (net (code "182") (name "unconnected-(J1D-HDMI0_TX2P_PORT-Pad333)") (class "Default")
      (node (ref "J1") (pin "333") (pinfunction "HDMI0_TX2P_PORT_333") (pintype "bidirectional"))
    )
    (net (code "183") (name "unconnected-(J1D-HDMI0_TX3N_PORT-Pad353)") (class "Default")
      (node (ref "J1") (pin "353") (pinfunction "HDMI0_TX3N_PORT_353") (pintype "bidirectional"))
    )
    (net (code "184") (name "unconnected-(J1D-HDMI0_TX3P_PORT-Pad351)") (class "Default")
      (node (ref "J1") (pin "351") (pinfunction "HDMI0_TX3P_PORT_351") (pintype "bidirectional"))
    )
    (net (code "185") (name "unconnected-(J1D-HDMI0_TX_ON_H-Pad369)") (class "Default")
      (node (ref "J1") (pin "369") (pinfunction "HDMI0_TX_ON_H_369") (pintype "bidirectional"))
    )
    (net (code "186") (name "unconnected-(J1D-HDMI0_TX_SBDN-Pad359)") (class "Default")
      (node (ref "J1") (pin "359") (pinfunction "HDMI0_TX_SBDN_359") (pintype "bidirectional"))
    )
    (net (code "187") (name "unconnected-(J1D-HDMI0_TX_SBDP-Pad357)") (class "Default")
      (node (ref "J1") (pin "357") (pinfunction "HDMI0_TX_SBDP_357") (pintype "bidirectional"))
    )
    (net (code "188") (name "unconnected-(J1D-HDMI1_TX0N_PORT-Pad317)") (class "Default")
      (node (ref "J1") (pin "317") (pinfunction "HDMI1_TX0N_PORT_317") (pintype "passive"))
    )
    (net (code "189") (name "unconnected-(J1D-HDMI1_TX0P_PORT-Pad315)") (class "Default")
      (node (ref "J1") (pin "315") (pinfunction "HDMI1_TX0P_PORT_315") (pintype "output"))
    )
    (net (code "190") (name "unconnected-(J1D-HDMI1_TX1N_PORT-Pad311)") (class "Default")
      (node (ref "J1") (pin "311") (pinfunction "HDMI1_TX1N_PORT_311") (pintype "output"))
    )
    (net (code "191") (name "unconnected-(J1D-HDMI1_TX1P_PORT-Pad309)") (class "Default")
      (node (ref "J1") (pin "309") (pinfunction "HDMI1_TX1P_PORT_309") (pintype "output"))
    )
    (net (code "192") (name "unconnected-(J1D-HDMI1_TX2N_PORT-Pad305)") (class "Default")
      (node (ref "J1") (pin "305") (pinfunction "HDMI1_TX2N_PORT_305") (pintype "output"))
    )
    (net (code "193") (name "unconnected-(J1D-HDMI1_TX2P_PORT-Pad303)") (class "Default")
      (node (ref "J1") (pin "303") (pinfunction "HDMI1_TX2P_PORT_303") (pintype "output"))
    )
    (net (code "194") (name "unconnected-(J1D-HDMI1_TX3N_PORT-Pad323)") (class "Default")
      (node (ref "J1") (pin "323") (pinfunction "HDMI1_TX3N_PORT_323") (pintype "output"))
    )
    (net (code "195") (name "unconnected-(J1D-HDMI1_TX3P_PORT-Pad321)") (class "Default")
      (node (ref "J1") (pin "321") (pinfunction "HDMI1_TX3P_PORT_321") (pintype "output"))
    )
    (net (code "196") (name "unconnected-(J1D-HDMI1_TX_ON_H-Pad377)") (class "Default")
      (node (ref "J1") (pin "377") (pinfunction "HDMI1_TX_ON_H_377") (pintype "bidirectional"))
    )
    (net (code "197") (name "unconnected-(J1D-HDMI1_TX_SBDN-Pad329)") (class "Default")
      (node (ref "J1") (pin "329") (pinfunction "HDMI1_TX_SBDN_329") (pintype "output"))
    )
    (net (code "198") (name "unconnected-(J1D-HDMI1_TX_SBDP-Pad327)") (class "Default")
      (node (ref "J1") (pin "327") (pinfunction "HDMI1_TX_SBDP_327") (pintype "output"))
    )
    (net (code "199") (name "unconnected-(J1D-HDMIIRX_HPDOUT_H-Pad378)") (class "Default")
      (node (ref "J1") (pin "378") (pinfunction "HDMIIRX_HPDOUT_H_378") (pintype "bidirectional"))
    )
    (net (code "200") (name "unconnected-(J1D-HDMITX0_CEC_M0-Pad367)") (class "Default")
      (node (ref "J1") (pin "367") (pinfunction "HDMITX0_CEC_M0_367") (pintype "bidirectional"))
    )
    (net (code "201") (name "unconnected-(J1D-HDMITX0_SCL_M0-Pad363)") (class "Default")
      (node (ref "J1") (pin "363") (pinfunction "HDMITX0_SCL_M0_363") (pintype "output"))
    )
    (net (code "202") (name "unconnected-(J1D-HDMITX0_SDA_M0-Pad365)") (class "Default")
      (node (ref "J1") (pin "365") (pinfunction "HDMITX0_SDA_M0_365") (pintype "bidirectional"))
    )
    (net (code "203") (name "unconnected-(J1D-HDMITX1_CEC_M2-Pad375)") (class "Default")
      (node (ref "J1") (pin "375") (pinfunction "HDMITX1_CEC_M2_375") (pintype "bidirectional"))
    )
    (net (code "204") (name "unconnected-(J1D-HDMITX1_SCL_M1-Pad371)") (class "Default")
      (node (ref "J1") (pin "371") (pinfunction "HDMITX1_SCL_M1_371") (pintype "output"))
    )
    (net (code "205") (name "unconnected-(J1D-HDMITX1_SDA_M1-Pad373)") (class "Default")
      (node (ref "J1") (pin "373") (pinfunction "HDMITX1_SDA_M1_373") (pintype "bidirectional"))
    )
    (net (code "206") (name "unconnected-(J1D-HDMI_RX_CEC-Pad376)") (class "Default")
      (node (ref "J1") (pin "376") (pinfunction "HDMI_RX_CEC_376") (pintype "bidirectional"))
    )
    (net (code "207") (name "unconnected-(J1D-HDMI_RX_CLKN_PORT-Pad348)") (class "Default")
      (node (ref "J1") (pin "348") (pinfunction "HDMI_RX_CLKN_PORT_348") (pintype "bidirectional"))
    )
    (net (code "208") (name "unconnected-(J1D-HDMI_RX_CLKP_PORT-Pad346)") (class "Default")
      (node (ref "J1") (pin "346") (pinfunction "HDMI_RX_CLKP_PORT_346") (pintype "bidirectional"))
    )
    (net (code "209") (name "unconnected-(J1D-HDMI_RX_D0N_PORT-Pad342)") (class "Default")
      (node (ref "J1") (pin "342") (pinfunction "HDMI_RX_D0N_PORT_342") (pintype "bidirectional"))
    )
    (net (code "210") (name "unconnected-(J1D-HDMI_RX_D0P_PORT-Pad340)") (class "Default")
      (node (ref "J1") (pin "340") (pinfunction "HDMI_RX_D0P_PORT_340") (pintype "bidirectional"))
    )
    (net (code "211") (name "unconnected-(J1D-HDMI_RX_D1N_PORT-Pad336)") (class "Default")
      (node (ref "J1") (pin "336") (pinfunction "HDMI_RX_D1N_PORT_336") (pintype "bidirectional"))
    )
    (net (code "212") (name "unconnected-(J1D-HDMI_RX_D1P_PORT-Pad334)") (class "Default")
      (node (ref "J1") (pin "334") (pinfunction "HDMI_RX_D1P_PORT_334") (pintype "bidirectional"))
    )
    (net (code "213") (name "unconnected-(J1D-HDMI_RX_D2N_PORT-Pad330)") (class "Default")
      (node (ref "J1") (pin "330") (pinfunction "HDMI_RX_D2N_PORT_330") (pintype "bidirectional"))
    )
    (net (code "214") (name "unconnected-(J1D-HDMI_RX_D2P_PORT-Pad328)") (class "Default")
      (node (ref "J1") (pin "328") (pinfunction "HDMI_RX_D2P_PORT_328") (pintype "bidirectional"))
    )
    (net (code "215") (name "unconnected-(J1D-HDMI_RX_SCL_M1-Pad372)") (class "Default")
      (node (ref "J1") (pin "372") (pinfunction "HDMI_RX_SCL_M1_372") (pintype "output"))
    )
    (net (code "216") (name "unconnected-(J1D-HDMI_RX_SDA_M1-Pad374)") (class "Default")
      (node (ref "J1") (pin "374") (pinfunction "HDMI_RX_SDA_M1_374") (pintype "bidirectional"))
    )
    (net (code "217") (name "unconnected-(J1D-SDMMC0_CMD-Pad356)") (class "Default")
      (node (ref "J1") (pin "356") (pinfunction "SDMMC0_CMD_356") (pintype "bidirectional"))
    )
    (net (code "218") (name "unconnected-(J1D-SDMMC0_D0-Pad364)") (class "Default")
      (node (ref "J1") (pin "364") (pinfunction "SDMMC0_D0_364") (pintype "bidirectional"))
    )
    (net (code "219") (name "unconnected-(J1D-SDMMC0_D1-Pad366)") (class "Default")
      (node (ref "J1") (pin "366") (pinfunction "SDMMC0_D1_366") (pintype "bidirectional"))
    )
    (net (code "220") (name "unconnected-(J1D-SDMMC0_D2-Pad352)") (class "Default")
      (node (ref "J1") (pin "352") (pinfunction "SDMMC0_D2_352") (pintype "bidirectional"))
    )
    (net (code "221") (name "unconnected-(J1D-SDMMC0_D3-Pad354)") (class "Default")
      (node (ref "J1") (pin "354") (pinfunction "SDMMC0_D3_354") (pintype "bidirectional"))
    )
    (net (code "222") (name "unconnected-(J1D-SD_CLK-Pad360)") (class "Default")
      (node (ref "J1") (pin "360") (pinfunction "SD_CLK_360") (pintype "output"))
    )
    (net (code "223") (name "unconnected-(J1D-TYPEC0_SBU1_OUT-Pad304)") (class "Default")
      (node (ref "J1") (pin "304") (pinfunction "TYPEC0_SBU1_OUT_304") (pintype "output"))
    )
    (net (code "224") (name "unconnected-(J1D-TYPEC0_SBU2_OUT-Pad306)") (class "Default")
      (node (ref "J1") (pin "306") (pinfunction "TYPEC0_SBU2_OUT_306") (pintype "output"))
    )
    (net (code "225") (name "unconnected-(J1D-TYPEC1_SBU1-Pad310)") (class "Default")
      (node (ref "J1") (pin "310") (pinfunction "TYPEC1_SBU1_310") (pintype "input"))
    )
    (net (code "226") (name "unconnected-(J1D-TYPEC1_SBU2-Pad312)") (class "Default")
      (node (ref "J1") (pin "312") (pinfunction "TYPEC1_SBU2_312") (pintype "output"))
    )
    (net (code "227") (name "unconnected-(J1D-USB20_HOST0_DM-Pad324)") (class "Default")
      (node (ref "J1") (pin "324") (pinfunction "USB20_HOST0_DM_324") (pintype "bidirectional"))
    )
    (net (code "228") (name "unconnected-(J1D-USB20_HOST0_DP-Pad322)") (class "Default")
      (node (ref "J1") (pin "322") (pinfunction "USB20_HOST0_DP_322") (pintype "bidirectional"))
    )
    (net (code "229") (name "unconnected-(J1D-USB20_HOST1_DM-Pad318)") (class "Default")
      (node (ref "J1") (pin "318") (pinfunction "USB20_HOST1_DM_318") (pintype "bidirectional"))
    )
    (net (code "230") (name "unconnected-(J1D-USB20_HOST1_DP-Pad316)") (class "Default")
      (node (ref "J1") (pin "316") (pinfunction "USB20_HOST1_DP_316") (pintype "bidirectional"))
    )
    (net (code "231") (name "unconnected-(J1D-VCC3V3_SD_S0-Pad358)") (class "Default")
      (node (ref "J1") (pin "358") (pinfunction "VCC3V3_SD_S0_358") (pintype "power_in"))
    )
  )
)
